# AFE.net
KiCad netlist of a schematic drawn in Altium Designer
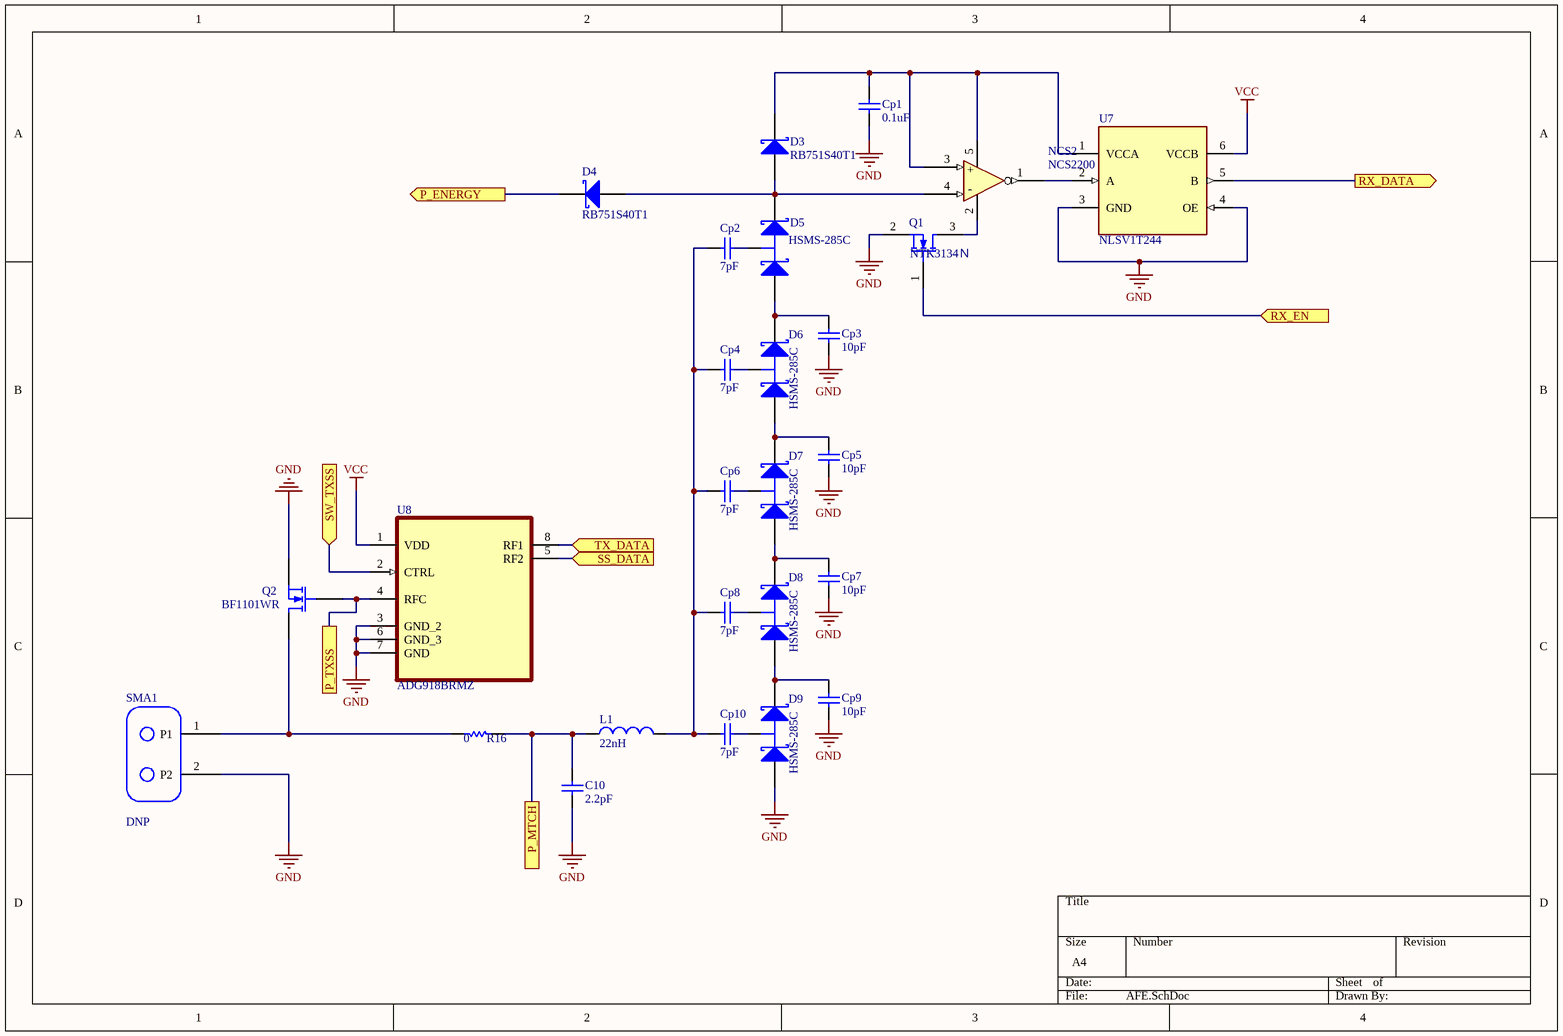
[diagram p0: AFE.SchDoc]

(export (version "E")
  (design (tool "Eeschema 10.0.6"))
  (components
    (comp (ref "C10")
      (value "2.2pF")
      (footprint "0805")
      (description "Ceramic Capacitor (Surface Mount)")
      (fields (field (name "DIGI-KEY PART NUMBER") "712-1289-1-ND") (field (name "MANUFACTURER") "Johanson"))
      (libsource (lib "Sensor") (part "Cap"))
    )
    (comp (ref "Cp1")
      (value "0.1uF")
      (footprint "0402")
      (description "Ceramic Capacitor (Surface Mount)")
      (fields (field (name "DIGI-KEY PART NUMBER") "712-1253-1-ND") (field (name "MANUFACTURER") "Johanson"))
      (libsource (lib "Sensor") (part "Cap"))
    )
    (comp (ref "Cp2")
      (value "7pF")
      (footprint "0402")
      (description "Ceramic Capacitor (Surface Mount)")
      (fields (field (name "DIGI-KEY PART NUMBER") "712-1253-1-ND") (field (name "MANUFACTURER") "Johanson"))
      (libsource (lib "Sensor") (part "Cap"))
    )
    (comp (ref "Cp3")
      (value "10pF")
      (footprint "0402")
      (description "Ceramic Capacitor (Surface Mount)")
      (fields (field (name "DIGI-KEY PART NUMBER") "712-1253-1-ND") (field (name "MANUFACTURER") "Johanson"))
      (libsource (lib "Sensor") (part "Cap"))
    )
    (comp (ref "Cp4")
      (value "7pF")
      (footprint "0402")
      (description "Ceramic Capacitor (Surface Mount)")
      (fields (field (name "DIGI-KEY PART NUMBER") "712-1253-1-ND") (field (name "MANUFACTURER") "Johanson"))
      (libsource (lib "Sensor") (part "Cap"))
    )
    (comp (ref "Cp5")
      (value "10pF")
      (footprint "0402")
      (description "Ceramic Capacitor (Surface Mount)")
      (fields (field (name "DIGI-KEY PART NUMBER") "712-1253-1-ND") (field (name "MANUFACTURER") "Johanson"))
      (libsource (lib "Sensor") (part "Cap"))
    )
    (comp (ref "Cp6")
      (value "7pF")
      (footprint "0402")
      (description "Ceramic Capacitor (Surface Mount)")
      (fields (field (name "DIGI-KEY PART NUMBER") "712-1253-1-ND") (field (name "MANUFACTURER") "Johanson"))
      (libsource (lib "Sensor") (part "Cap"))
    )
    (comp (ref "Cp7")
      (value "10pF")
      (footprint "0402")
      (description "Ceramic Capacitor (Surface Mount)")
      (fields (field (name "DIGI-KEY PART NUMBER") "712-1253-1-ND") (field (name "MANUFACTURER") "Johanson"))
      (libsource (lib "Sensor") (part "Cap"))
    )
    (comp (ref "Cp8")
      (value "7pF")
      (footprint "0402")
      (description "Ceramic Capacitor (Surface Mount)")
      (fields (field (name "DIGI-KEY PART NUMBER") "712-1253-1-ND") (field (name "MANUFACTURER") "Johanson"))
      (libsource (lib "Sensor") (part "Cap"))
    )
    (comp (ref "Cp9")
      (value "10pF")
      (footprint "0402")
      (description "Ceramic Capacitor (Surface Mount)")
      (fields (field (name "DIGI-KEY PART NUMBER") "712-1253-1-ND") (field (name "MANUFACTURER") "Johanson"))
      (libsource (lib "Sensor") (part "Cap"))
    )
    (comp (ref "Cp10")
      (value "7pF")
      (footprint "0402")
      (description "Ceramic Capacitor (Surface Mount)")
      (fields (field (name "DIGI-KEY PART NUMBER") "712-1253-1-ND") (field (name "MANUFACTURER") "Johanson"))
      (libsource (lib "Sensor") (part "Cap"))
    )
    (comp (ref "D3")
      (value "RB751S40T1")
      (footprint "SOD-523")
      (description "Schottky Diode")
      (fields (field (name "PUBLISHER") "Altium Limited"))
      (libsource (lib "Sensor") (part "RB751S40T1"))
    )
    (comp (ref "D4")
      (value "RB751S40T1")
      (footprint "SOD-523")
      (description "Schottky Diode")
      (fields (field (name "PUBLISHER") "Altium Limited"))
      (libsource (lib "Sensor") (part "RB751S40T1"))
    )
    (comp (ref "D5")
      (value "HSMS-285C")
      (footprint "SOT-323, HSMS-285C")
      (description "Agilent Schottky Diode, Two in Series, Small Package SOT-323")
      (fields
        (field (name "DIGI-KEY PART NUMBER") "516-2558-ND")
        (field (name "MANUFACTURER") "Avago Technologies US Inc.")
      )
      (libsource (lib "Sensor") (part "HSMS-285C"))
    )
    (comp (ref "D6")
      (value "HSMS-285C")
      (footprint "SOT-323, HSMS-285C")
      (description "Agilent Schottky Diode, Two in Series, Small Package SOT-323")
      (fields
        (field (name "DIGI-KEY PART NUMBER") "516-2558-ND")
        (field (name "MANUFACTURER") "Avago Technologies US Inc.")
      )
      (libsource (lib "Sensor") (part "HSMS-285C"))
    )
    (comp (ref "D7")
      (value "HSMS-285C")
      (footprint "SOT-323, HSMS-285C")
      (description "Agilent Schottky Diode, Two in Series, Small Package SOT-323")
      (fields
        (field (name "DIGI-KEY PART NUMBER") "516-2558-ND")
        (field (name "MANUFACTURER") "Avago Technologies US Inc.")
      )
      (libsource (lib "Sensor") (part "HSMS-285C"))
    )
    (comp (ref "D8")
      (value "HSMS-285C")
      (footprint "SOT-323, HSMS-285C")
      (description "Agilent Schottky Diode, Two in Series, Small Package SOT-323")
      (fields
        (field (name "DIGI-KEY PART NUMBER") "516-2558-ND")
        (field (name "MANUFACTURER") "Avago Technologies US Inc.")
      )
      (libsource (lib "Sensor") (part "HSMS-285C"))
    )
    (comp (ref "D9")
      (value "HSMS-285C")
      (footprint "SOT-323, HSMS-285C")
      (description "Agilent Schottky Diode, Two in Series, Small Package SOT-323")
      (fields
        (field (name "DIGI-KEY PART NUMBER") "516-2558-ND")
        (field (name "MANUFACTURER") "Avago Technologies US Inc.")
      )
      (libsource (lib "Sensor") (part "HSMS-285C"))
    )
    (comp (ref "L1")
      (value "22nH")
      (footprint "0805")
      (description "Inductor (Surface Mount)")
      (fields
        (field (name "MANUFACTURER") "Coilcraft (http://www.coilcraft.com/0402cs.cfm)")
        (field (name "MANUFACTURER PART NUMBER") "0402CS-16NX_LU")
      )
      (libsource (lib "Sensor") (part "Ind"))
    )
    (comp (ref "NCS2")
      (value "NCS2200")
      (footprint "SC70-5")
      (description "Comparator: On Semi 10uA Comparator")
      (fields
        (field (name "DIGI-KEY PART NUMBER") "NCS2200SQ2T2GOSTR-ND")
        (field (name "MANUFACTURER") "ON Semiconductor")
      )
      (libsource (lib "Sensor") (part "NCS2200"))
    )
    (comp (ref "Q1")
      (value "NTK3134Ｎ")
      (footprint "SOT40P120X55-3N")
      (libsource (lib "Sensor") (part "NTK3134Ｎ"))
    )
    (comp (ref "Q2")
      (value "BF1101WR")
      (footprint "SOT343R")
      (description "N-Channel Dual-Gate Mos-Fets MOSFET, SOT343R")
      (fields
        (field (name "DIGI-KEY PART NUMBER") "568-6140-1-ND")
        (field (name "MANUFACTURER PART NUMBER") "BF1101WR,115")
      )
      (libsource (lib "Sensor") (part "BF1101WR"))
    )
    (comp (ref "R16")
      (value "0")
      (footprint "0805")
      (description "Chip Resistor (Surface Mount)")
      (fields
        (field (name "MANUFACTURER") "Panasonic")
        (field (name "MANUFACTURER PART NUMBER") "ERJ-2RKF4702X")
      )
      (libsource (lib "Sensor") (part "Res"))
    )
    (comp (ref "SMA1")
      (value "~")
      (footprint "SMA - Hole - 2 Pin")
      (description "Two pin SMA connector wisp")
      (fields (field (name "DNP") "DNP"))
      (libsource (lib "Sensor") (part "SMA - Hole - 2 Pin"))
    )
    (comp (ref "U7")
      (value "NLSV1T244")
      (footprint "UDFN6")
      (description "Level Shifter: 1-Bit Dual-Supply Non-Inverting Level Translator")
      (fields
        (field (name "DIGI-KEY PART NUMBER") "NLSV1T244MUTBG-ND")
        (field (name "MANUFACTURER PART NUMBER") "NLSV1T244MUTBG")
      )
      (libsource (lib "Sensor") (part "NLSV1T244"))
    )
    (comp (ref "U8")
      (value "ADG918BRMZ")
      (footprint "SOP65P490X110-8N")
      (description "RF Switch Single Pole 0 MHz to 4GHz 34dB 8-Pin MSOP")
      (fields (field (name "MF") "Analog Devices") (field (name "DIGI-KEY_PART_NUMBER") "ADG918BRMZ-ND"))
      (libsource (lib "Sensor") (part "ADG918BRMZ"))
    )
  )
  (nets
    (net (code "1") (name "/P_ENERGY") (class "Default")
      (node (ref "D4") (pin "1") (pinfunction "C_1") (pintype "passive"))
    )
    (net (code "2") (name "/P_MTCH") (class "Default")
      (node (ref "C10") (pin "2") (pinfunction "2_2") (pintype "passive"))
      (node (ref "L1") (pin "1") (pinfunction "1_1") (pintype "passive"))
      (node (ref "R16") (pin "1") (pinfunction "1_1") (pintype "passive"))
    )
    (net (code "3") (name "/P_TXSS") (class "Default")
      (node (ref "Q2") (pin "3") (pinfunction "G_3") (pintype "passive"))
      (node (ref "U8") (pin "4") (pinfunction "RFC_4") (pintype "passive"))
    )
    (net (code "4") (name "/RX_DATA") (class "Default")
      (node (ref "U7") (pin "5") (pinfunction "B_5") (pintype "output"))
    )
    (net (code "5") (name "/RX_EN") (class "Default")
      (node (ref "Q1") (pin "1") (pinfunction "G_1") (pintype "passive"))
    )
    (net (code "6") (name "/SS_DATA") (class "Default")
      (node (ref "U8") (pin "5") (pinfunction "RF2_5") (pintype "passive"))
    )
    (net (code "7") (name "/SW_TXSS") (class "Default")
      (node (ref "U8") (pin "2") (pinfunction "CTRL_2") (pintype "input"))
    )
    (net (code "8") (name "/TX_DATA") (class "Default")
      (node (ref "U8") (pin "8") (pinfunction "RF1_8") (pintype "passive"))
    )
    (net (code "9") (name "GND") (class "Default")
      (node (ref "C10") (pin "1") (pinfunction "1_1") (pintype "passive"))
      (node (ref "Cp1") (pin "2") (pinfunction "2_2") (pintype "passive"))
      (node (ref "Cp3") (pin "2") (pinfunction "2_2") (pintype "passive"))
      (node (ref "Cp5") (pin "2") (pinfunction "2_2") (pintype "passive"))
      (node (ref "Cp7") (pin "2") (pinfunction "2_2") (pintype "passive"))
      (node (ref "Cp9") (pin "2") (pinfunction "2_2") (pintype "passive"))
      (node (ref "D9") (pin "1") (pinfunction "A_1") (pintype "passive"))
      (node (ref "Q1") (pin "2") (pinfunction "S_2") (pintype "passive"))
      (node (ref "Q2") (pin "1") (pinfunction "S_1") (pintype "passive"))
      (node (ref "SMA1") (pin "2") (pinfunction "P2_2") (pintype "passive"))
      (node (ref "U7") (pin "3") (pinfunction "GND_3") (pintype "power_in"))
      (node (ref "U7") (pin "4") (pinfunction "OE_4") (pintype "input"))
      (node (ref "U8") (pin "3") (pinfunction "GND_2_3") (pintype "passive"))
      (node (ref "U8") (pin "6") (pinfunction "GND_3_6") (pintype "passive"))
      (node (ref "U8") (pin "7") (pinfunction "GND_7") (pintype "passive"))
    )
    (net (code "10") (name "Net-(Cp10-Pad2)") (class "Default")
      (node (ref "Cp10") (pin "2") (pinfunction "2_2") (pintype "passive"))
      (node (ref "Cp2") (pin "2") (pinfunction "2_2") (pintype "passive"))
      (node (ref "Cp4") (pin "2") (pinfunction "2_2") (pintype "passive"))
      (node (ref "Cp6") (pin "2") (pinfunction "2_2") (pintype "passive"))
      (node (ref "Cp8") (pin "2") (pinfunction "2_2") (pintype "passive"))
      (node (ref "L1") (pin "2") (pinfunction "2_2") (pintype "passive"))
    )
    (net (code "11") (name "Net-(D3-A)") (class "Default")
      (node (ref "D3") (pin "2") (pinfunction "A_2") (pintype "passive"))
      (node (ref "D4") (pin "2") (pinfunction "A_2") (pintype "passive"))
      (node (ref "D5") (pin "2") (pinfunction "K_2") (pintype "passive"))
      (node (ref "NCS2") (pin "4") (pinfunction "In-_4") (pintype "input"))
    )
    (net (code "12") (name "Net-(D3-C)") (class "Default")
      (node (ref "Cp1") (pin "1") (pinfunction "1_1") (pintype "passive"))
      (node (ref "D3") (pin "1") (pinfunction "C_1") (pintype "passive"))
      (node (ref "NCS2") (pin "3") (pinfunction "IN+_3") (pintype "input"))
      (node (ref "NCS2") (pin "5") (pinfunction "VDD_5") (pintype "power_in"))
      (node (ref "U7") (pin "1") (pinfunction "VCCA_1") (pintype "power_in"))
    )
    (net (code "13") (name "Net-(D5-A)") (class "Default")
      (node (ref "Cp3") (pin "1") (pinfunction "1_1") (pintype "passive"))
      (node (ref "D5") (pin "1") (pinfunction "A_1") (pintype "passive"))
      (node (ref "D6") (pin "2") (pinfunction "K_2") (pintype "passive"))
    )
    (net (code "14") (name "Net-(D5-C)") (class "Default")
      (node (ref "Cp2") (pin "1") (pinfunction "1_1") (pintype "passive"))
      (node (ref "D5") (pin "3") (pinfunction "C_3") (pintype "passive"))
    )
    (net (code "15") (name "Net-(D6-A)") (class "Default")
      (node (ref "Cp5") (pin "1") (pinfunction "1_1") (pintype "passive"))
      (node (ref "D6") (pin "1") (pinfunction "A_1") (pintype "passive"))
      (node (ref "D7") (pin "2") (pinfunction "K_2") (pintype "passive"))
    )
    (net (code "16") (name "Net-(D6-C)") (class "Default")
      (node (ref "Cp4") (pin "1") (pinfunction "1_1") (pintype "passive"))
      (node (ref "D6") (pin "3") (pinfunction "C_3") (pintype "passive"))
    )
    (net (code "17") (name "Net-(D7-A)") (class "Default")
      (node (ref "Cp7") (pin "1") (pinfunction "1_1") (pintype "passive"))
      (node (ref "D7") (pin "1") (pinfunction "A_1") (pintype "passive"))
      (node (ref "D8") (pin "2") (pinfunction "K_2") (pintype "passive"))
    )
    (net (code "18") (name "Net-(D7-C)") (class "Default")
      (node (ref "Cp6") (pin "1") (pinfunction "1_1") (pintype "passive"))
      (node (ref "D7") (pin "3") (pinfunction "C_3") (pintype "passive"))
    )
    (net (code "19") (name "Net-(D8-A)") (class "Default")
      (node (ref "Cp9") (pin "1") (pinfunction "1_1") (pintype "passive"))
      (node (ref "D8") (pin "1") (pinfunction "A_1") (pintype "passive"))
      (node (ref "D9") (pin "2") (pinfunction "K_2") (pintype "passive"))
    )
    (net (code "20") (name "Net-(D8-C)") (class "Default")
      (node (ref "Cp8") (pin "1") (pinfunction "1_1") (pintype "passive"))
      (node (ref "D8") (pin "3") (pinfunction "C_3") (pintype "passive"))
    )
    (net (code "21") (name "Net-(D9-C)") (class "Default")
      (node (ref "Cp10") (pin "1") (pinfunction "1_1") (pintype "passive"))
      (node (ref "D9") (pin "3") (pinfunction "C_3") (pintype "passive"))
    )
    (net (code "22") (name "Net-(NCS2-GND)") (class "Default")
      (node (ref "NCS2") (pin "2") (pinfunction "GND_2") (pintype "power_in"))
      (node (ref "Q1") (pin "3") (pinfunction "D_3") (pintype "passive"))
    )
    (net (code "23") (name "Net-(NCS2-OUT)") (class "Default")
      (node (ref "NCS2") (pin "1") (pinfunction "OUT_1") (pintype "output"))
      (node (ref "U7") (pin "2") (pinfunction "A_2") (pintype "input"))
    )
    (net (code "24") (name "Net-(Q2-D)") (class "Default")
      (node (ref "Q2") (pin "2") (pinfunction "D_2") (pintype "passive"))
      (node (ref "R16") (pin "2") (pinfunction "2_2") (pintype "passive"))
      (node (ref "SMA1") (pin "1") (pinfunction "P1_1") (pintype "passive"))
    )
    (net (code "25") (name "VCC") (class "Default")
      (node (ref "U7") (pin "6") (pinfunction "VCCB_6") (pintype "power_in"))
      (node (ref "U8") (pin "1") (pinfunction "VDD_1") (pintype "power_in"))
    )
  )
)
